# 1-Schematic_EEPROM_Writer.net
KiCad netlist of a schematic drawn in EasyEDA
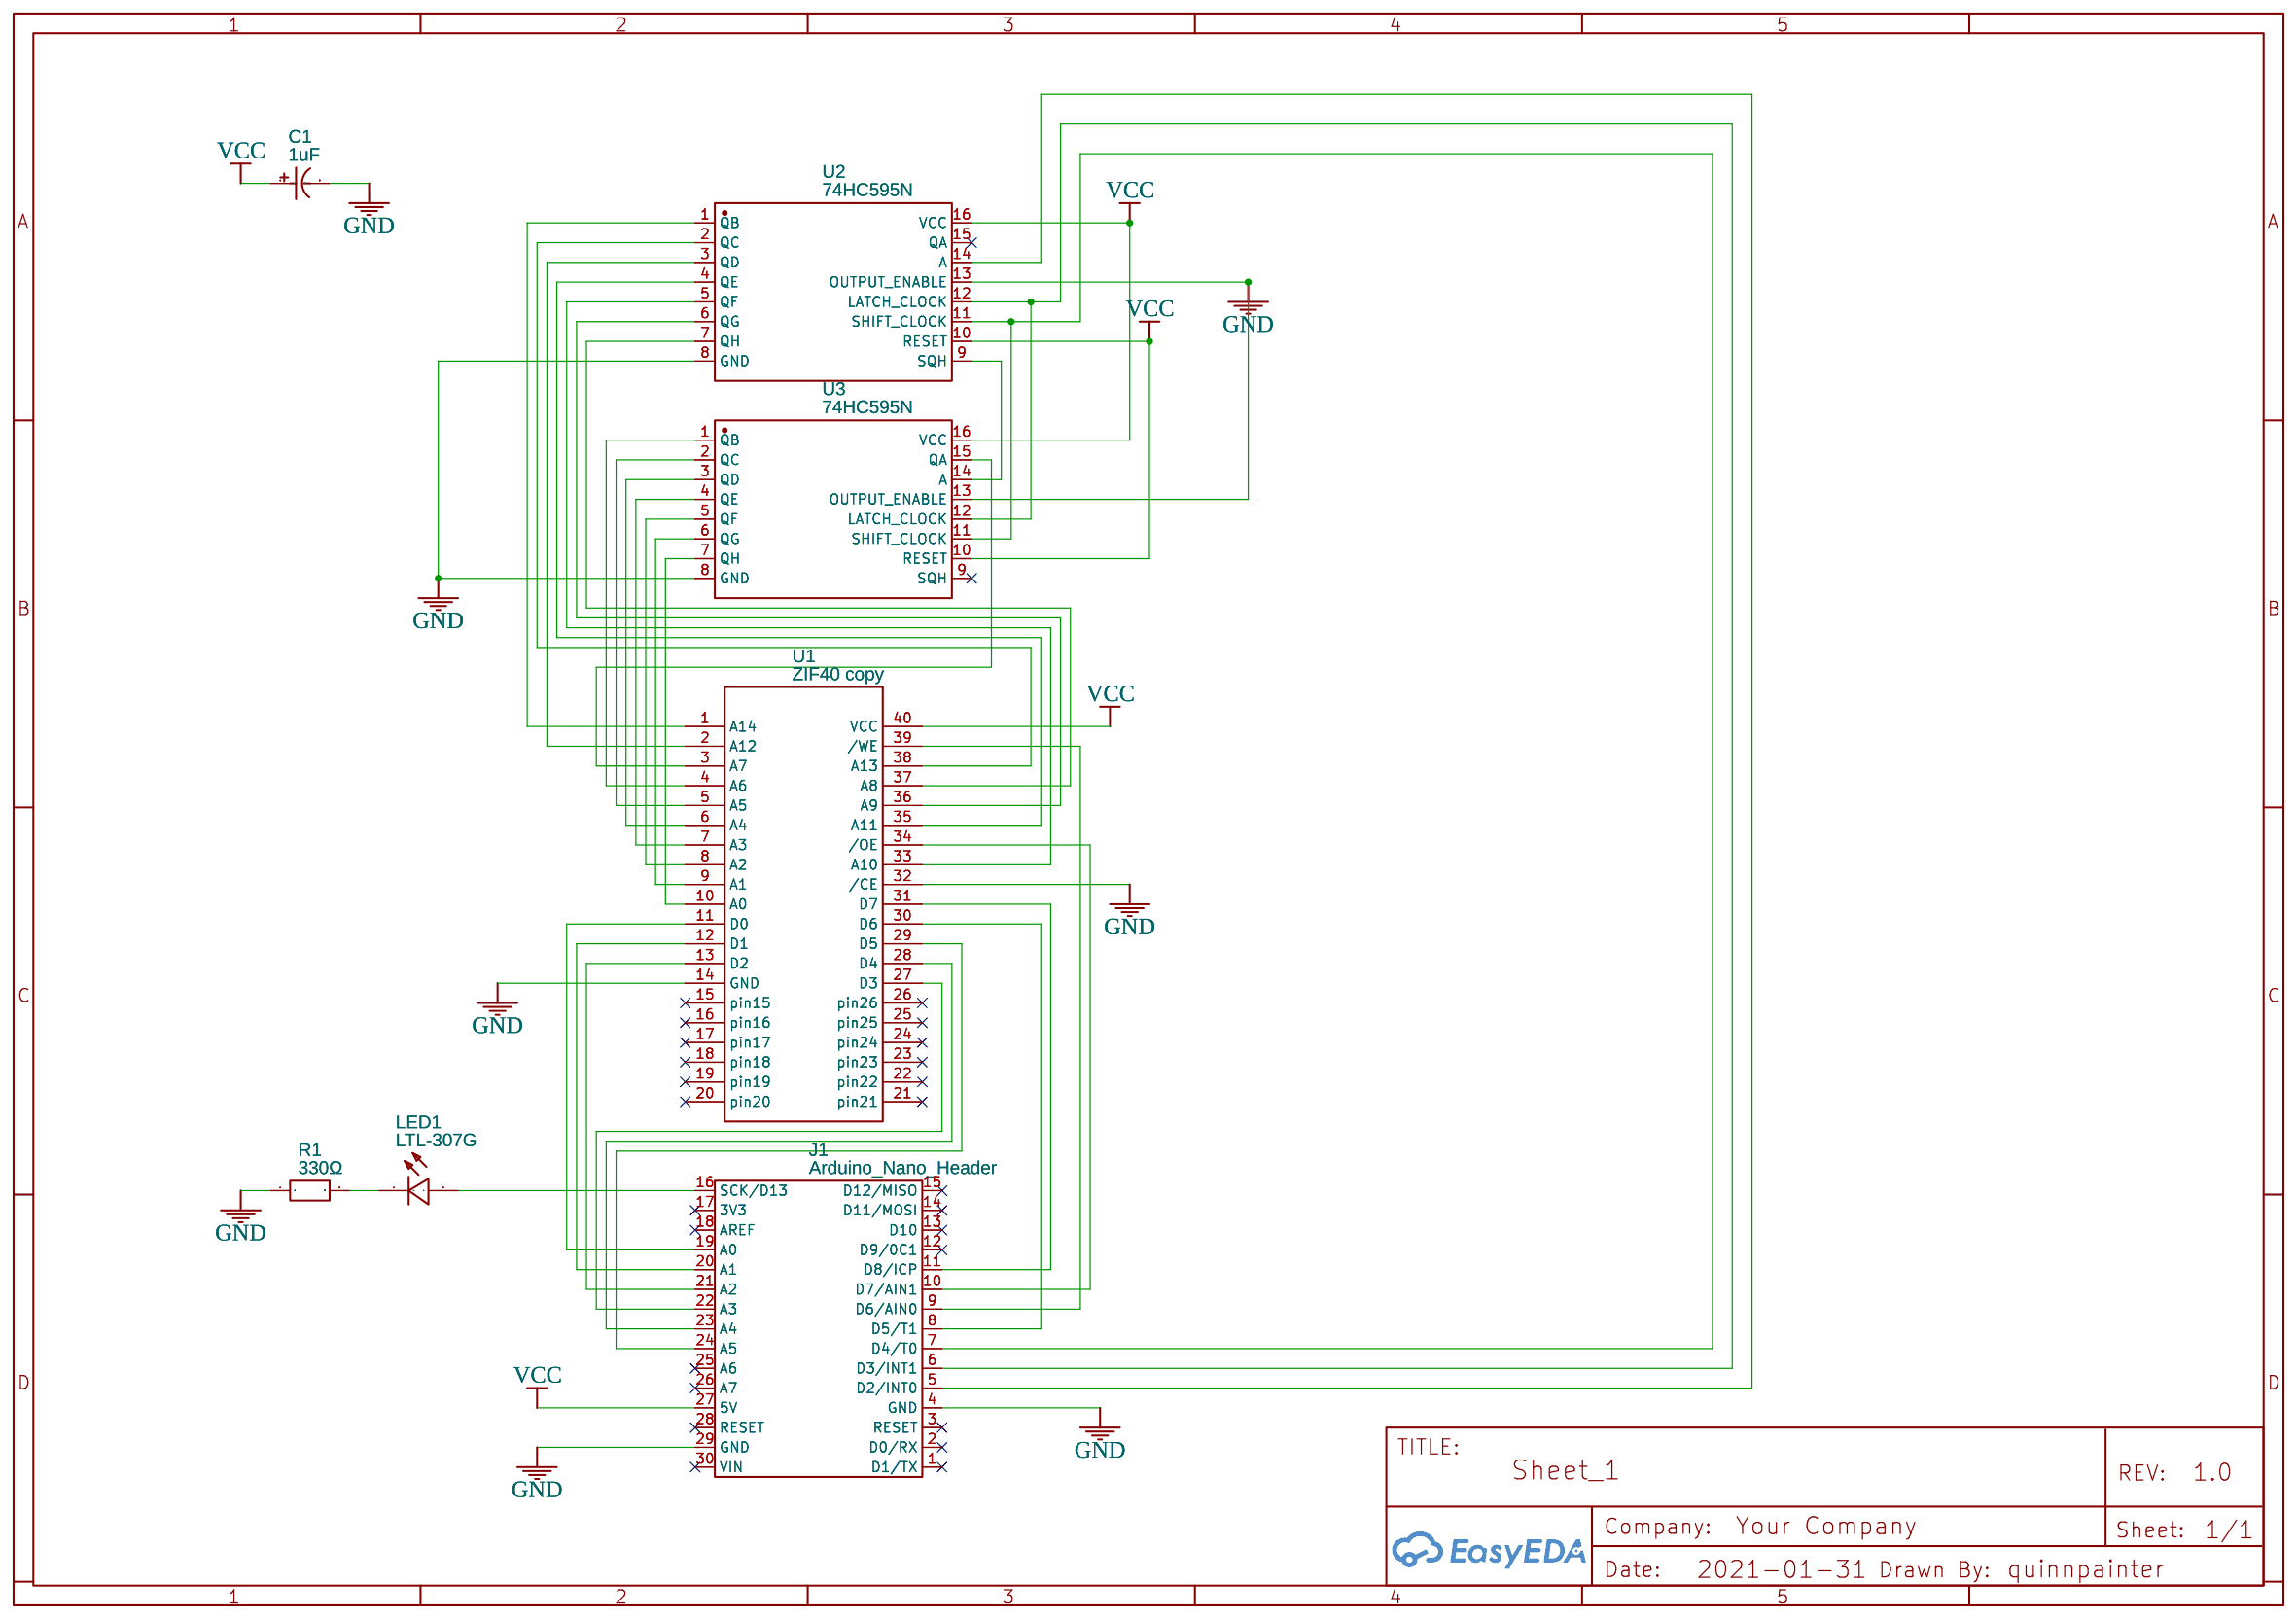
[diagram p0: schematic sheet]

(export (version "E")
  (design (tool "Eeschema 10.0.6"))
  (components
    (comp (ref "C1")
      (value "1uF")
      (fields
        (field (name "BOM_Manufacturer Part") "1uF 50V 4*5")
        (field (name "BOM_Supplier Part") "C47848")
      )
      (libsource (lib "") (part "1uF 50V 4*5"))
    )
    (comp (ref "J1") (value "Arduino_Nano_Header") (libsource (lib "") (part "Arduino_Nano_Header")))
    (comp (ref "LED1")
      (value "LTL-307G")
      (fields (field (name "BOM_Supplier Part") "C125080"))
      (libsource (lib "") (part "LTL-307G"))
    )
    (comp (ref "R1")
      (value "330Ω")
      (fields
        (field (name "BOM_Manufacturer Part") "MF1/4W-330Ω±1%T52")
        (field (name "BOM_Supplier Part") "C713986")
      )
      (libsource (lib "") (part "MF1/4W-330Ω±1%T52"))
    )
    (comp (ref "U1") (value "ZIF40 copy") (libsource (lib "") (part "ZIF40 copy")))
    (comp (ref "U2")
      (value "74HC595N")
      (fields (field (name "BOM_Supplier Part") "C507175"))
      (libsource (lib "") (part "74HC595N"))
    )
    (comp (ref "U3")
      (value "74HC595N")
      (fields (field (name "BOM_Supplier Part") "C507175"))
      (libsource (lib "") (part "74HC595N"))
    )
  )
  (nets
    (net (code "1") (name "GND") (class "Default")
      (node (ref "C1") (pin "2") (pinfunction "2_2") (pintype "input"))
      (node (ref "J1") (pin "29") (pinfunction "GND_29") (pintype "unspecified"))
      (node (ref "J1") (pin "4") (pinfunction "GND_4") (pintype "unspecified"))
      (node (ref "R1") (pin "1") (pinfunction "1_1") (pintype "unspecified"))
      (node (ref "U1") (pin "14") (pinfunction "GND_14") (pintype "output"))
      (node (ref "U1") (pin "32") (pinfunction "/CE_32") (pintype "bidirectional"))
      (node (ref "U2") (pin "13") (pinfunction "OUTPUT_ENABLE_13") (pintype "unspecified"))
      (node (ref "U2") (pin "8") (pinfunction "GND_8") (pintype "unspecified"))
      (node (ref "U3") (pin "13") (pinfunction "OUTPUT_ENABLE_13") (pintype "unspecified"))
      (node (ref "U3") (pin "8") (pinfunction "GND_8") (pintype "unspecified"))
    )
    (net (code "2") (name "Net-(J1-A0)") (class "Default")
      (node (ref "J1") (pin "19") (pinfunction "A0_19") (pintype "unspecified"))
      (node (ref "U1") (pin "11") (pinfunction "D0_11") (pintype "passive"))
    )
    (net (code "3") (name "Net-(J1-A1)") (class "Default")
      (node (ref "J1") (pin "20") (pinfunction "A1_20") (pintype "unspecified"))
      (node (ref "U1") (pin "12") (pinfunction "D1_12") (pintype "unspecified"))
    )
    (net (code "4") (name "Net-(J1-A2)") (class "Default")
      (node (ref "J1") (pin "21") (pinfunction "A2_21") (pintype "unspecified"))
      (node (ref "U1") (pin "13") (pinfunction "D2_13") (pintype "output"))
    )
    (net (code "5") (name "Net-(J1-A3)") (class "Default")
      (node (ref "J1") (pin "22") (pinfunction "A3_22") (pintype "unspecified"))
      (node (ref "U1") (pin "27") (pinfunction "D3_27") (pintype "unspecified"))
    )
    (net (code "6") (name "Net-(J1-A4)") (class "Default")
      (node (ref "J1") (pin "23") (pinfunction "A4_23") (pintype "unspecified"))
      (node (ref "U1") (pin "28") (pinfunction "D4_28") (pintype "passive"))
    )
    (net (code "7") (name "Net-(J1-A5)") (class "Default")
      (node (ref "J1") (pin "24") (pinfunction "A5_24") (pintype "unspecified"))
      (node (ref "U1") (pin "29") (pinfunction "D5_29") (pintype "bidirectional"))
    )
    (net (code "8") (name "Net-(J1-D2{slash}INT0)") (class "Default")
      (node (ref "J1") (pin "5") (pinfunction "D2/INT0_5") (pintype "unspecified"))
      (node (ref "U2") (pin "14") (pinfunction "A_14") (pintype "unspecified"))
    )
    (net (code "9") (name "Net-(J1-D3{slash}INT1)") (class "Default")
      (node (ref "J1") (pin "6") (pinfunction "D3/INT1_6") (pintype "unspecified"))
      (node (ref "U2") (pin "12") (pinfunction "LATCH_CLOCK_12") (pintype "unspecified"))
      (node (ref "U3") (pin "12") (pinfunction "LATCH_CLOCK_12") (pintype "unspecified"))
    )
    (net (code "10") (name "Net-(J1-D4{slash}T0)") (class "Default")
      (node (ref "J1") (pin "7") (pinfunction "D4/T0_7") (pintype "unspecified"))
      (node (ref "U2") (pin "11") (pinfunction "SHIFT_CLOCK_11") (pintype "unspecified"))
      (node (ref "U3") (pin "11") (pinfunction "SHIFT_CLOCK_11") (pintype "unspecified"))
    )
    (net (code "11") (name "Net-(J1-D5{slash}T1)") (class "Default")
      (node (ref "J1") (pin "8") (pinfunction "D5/T1_8") (pintype "unspecified"))
      (node (ref "U1") (pin "30") (pinfunction "D6_30") (pintype "bidirectional"))
    )
    (net (code "12") (name "Net-(J1-D6{slash}AIN0)") (class "Default")
      (node (ref "J1") (pin "9") (pinfunction "D6/AIN0_9") (pintype "unspecified"))
      (node (ref "U1") (pin "39") (pinfunction "/WE_39") (pintype "unspecified"))
    )
    (net (code "13") (name "Net-(J1-D7{slash}AIN1)") (class "Default")
      (node (ref "J1") (pin "10") (pinfunction "D7/AIN1_10") (pintype "unspecified"))
      (node (ref "U1") (pin "34") (pinfunction "/OE_34") (pintype "bidirectional"))
    )
    (net (code "14") (name "Net-(J1-D8{slash}ICP)") (class "Default")
      (node (ref "J1") (pin "11") (pinfunction "D8/ICP_11") (pintype "unspecified"))
      (node (ref "U1") (pin "31") (pinfunction "D7_31") (pintype "bidirectional"))
    )
    (net (code "15") (name "Net-(J1-SCK{slash}D13)") (class "Default")
      (node (ref "J1") (pin "16") (pinfunction "SCK/D13_16") (pintype "unspecified"))
      (node (ref "LED1") (pin "2") (pinfunction "+_2") (pintype "unspecified"))
    )
    (net (code "16") (name "Net-(LED1--)") (class "Default")
      (node (ref "LED1") (pin "1") (pinfunction "-_1") (pintype "unspecified"))
      (node (ref "R1") (pin "2") (pinfunction "2_2") (pintype "unspecified"))
    )
    (net (code "17") (name "Net-(U1-A0)") (class "Default")
      (node (ref "U1") (pin "10") (pinfunction "A0_10") (pintype "unspecified"))
      (node (ref "U3") (pin "7") (pinfunction "QH_7") (pintype "unspecified"))
    )
    (net (code "18") (name "Net-(U1-A1)") (class "Default")
      (node (ref "U1") (pin "9") (pinfunction "A1_9") (pintype "unspecified"))
      (node (ref "U3") (pin "6") (pinfunction "QG_6") (pintype "unspecified"))
    )
    (net (code "19") (name "Net-(U1-A2)") (class "Default")
      (node (ref "U1") (pin "8") (pinfunction "A2_8") (pintype "output"))
      (node (ref "U3") (pin "5") (pinfunction "QF_5") (pintype "unspecified"))
    )
    (net (code "20") (name "Net-(U1-A3)") (class "Default")
      (node (ref "U1") (pin "7") (pinfunction "A3_7") (pintype "unspecified"))
      (node (ref "U3") (pin "4") (pinfunction "QE_4") (pintype "unspecified"))
    )
    (net (code "21") (name "Net-(U1-A4)") (class "Default")
      (node (ref "U1") (pin "6") (pinfunction "A4_6") (pintype "unspecified"))
      (node (ref "U3") (pin "3") (pinfunction "QD_3") (pintype "unspecified"))
    )
    (net (code "22") (name "Net-(U1-A5)") (class "Default")
      (node (ref "U1") (pin "5") (pinfunction "A5_5") (pintype "unspecified"))
      (node (ref "U3") (pin "2") (pinfunction "QC_2") (pintype "unspecified"))
    )
    (net (code "23") (name "Net-(U1-A6)") (class "Default")
      (node (ref "U1") (pin "4") (pinfunction "A6_4") (pintype "unspecified"))
      (node (ref "U3") (pin "1") (pinfunction "QB_1") (pintype "unspecified"))
    )
    (net (code "24") (name "Net-(U1-A7)") (class "Default")
      (node (ref "U1") (pin "3") (pinfunction "A7_3") (pintype "unspecified"))
      (node (ref "U3") (pin "15") (pinfunction "QA_15") (pintype "unspecified"))
    )
    (net (code "25") (name "Net-(U1-A8)") (class "Default")
      (node (ref "U1") (pin "37") (pinfunction "A8_37") (pintype "unspecified"))
      (node (ref "U2") (pin "7") (pinfunction "QH_7") (pintype "unspecified"))
    )
    (net (code "26") (name "Net-(U1-A9)") (class "Default")
      (node (ref "U1") (pin "36") (pinfunction "A9_36") (pintype "bidirectional"))
      (node (ref "U2") (pin "6") (pinfunction "QG_6") (pintype "unspecified"))
    )
    (net (code "27") (name "Net-(U1-A10)") (class "Default")
      (node (ref "U1") (pin "33") (pinfunction "A10_33") (pintype "bidirectional"))
      (node (ref "U2") (pin "5") (pinfunction "QF_5") (pintype "unspecified"))
    )
    (net (code "28") (name "Net-(U1-A11)") (class "Default")
      (node (ref "U1") (pin "35") (pinfunction "A11_35") (pintype "bidirectional"))
      (node (ref "U2") (pin "4") (pinfunction "QE_4") (pintype "unspecified"))
    )
    (net (code "29") (name "Net-(U1-A12)") (class "Default")
      (node (ref "U1") (pin "2") (pinfunction "A12_2") (pintype "unspecified"))
      (node (ref "U2") (pin "3") (pinfunction "QD_3") (pintype "unspecified"))
    )
    (net (code "30") (name "Net-(U1-A13)") (class "Default")
      (node (ref "U1") (pin "38") (pinfunction "A13_38") (pintype "output"))
      (node (ref "U2") (pin "2") (pinfunction "QC_2") (pintype "unspecified"))
    )
    (net (code "31") (name "Net-(U1-A14)") (class "Default")
      (node (ref "U1") (pin "1") (pinfunction "A14_1") (pintype "unspecified"))
      (node (ref "U2") (pin "1") (pinfunction "QB_1") (pintype "unspecified"))
    )
    (net (code "32") (name "Net-(U2-SQH)") (class "Default")
      (node (ref "U2") (pin "9") (pinfunction "SQH_9") (pintype "unspecified"))
      (node (ref "U3") (pin "14") (pinfunction "A_14") (pintype "unspecified"))
    )
    (net (code "33") (name "VCC") (class "Default")
      (node (ref "C1") (pin "1") (pinfunction "1_1") (pintype "input"))
      (node (ref "J1") (pin "27") (pinfunction "5V_27") (pintype "unspecified"))
      (node (ref "U1") (pin "40") (pinfunction "VCC_40") (pintype "unspecified"))
      (node (ref "U2") (pin "10") (pinfunction "RESET_10") (pintype "unspecified"))
      (node (ref "U2") (pin "16") (pinfunction "VCC_16") (pintype "unspecified"))
      (node (ref "U3") (pin "10") (pinfunction "RESET_10") (pintype "unspecified"))
      (node (ref "U3") (pin "16") (pinfunction "VCC_16") (pintype "unspecified"))
    )
    (net (code "34") (name "unconnected-(J1-3V3-Pad17)") (class "Default")
      (node (ref "J1") (pin "17") (pinfunction "3V3_17") (pintype "unspecified+no_connect"))
    )
    (net (code "35") (name "unconnected-(J1-A6-Pad25)") (class "Default")
      (node (ref "J1") (pin "25") (pinfunction "A6_25") (pintype "unspecified+no_connect"))
    )
    (net (code "36") (name "unconnected-(J1-A7-Pad26)") (class "Default")
      (node (ref "J1") (pin "26") (pinfunction "A7_26") (pintype "unspecified+no_connect"))
    )
    (net (code "37") (name "unconnected-(J1-AREF-Pad18)") (class "Default")
      (node (ref "J1") (pin "18") (pinfunction "AREF_18") (pintype "unspecified+no_connect"))
    )
    (net (code "38") (name "unconnected-(J1-D0{slash}RX-Pad2)") (class "Default")
      (node (ref "J1") (pin "2") (pinfunction "D0/RX_2") (pintype "unspecified+no_connect"))
    )
    (net (code "39") (name "unconnected-(J1-D1{slash}TX-Pad1)") (class "Default")
      (node (ref "J1") (pin "1") (pinfunction "D1/TX_1") (pintype "unspecified+no_connect"))
    )
    (net (code "40") (name "unconnected-(J1-D9{slash}0C1-Pad12)") (class "Default")
      (node (ref "J1") (pin "12") (pinfunction "D9/0C1_12") (pintype "unspecified+no_connect"))
    )
    (net (code "41") (name "unconnected-(J1-D10-Pad13)") (class "Default")
      (node (ref "J1") (pin "13") (pinfunction "D10_13") (pintype "unspecified+no_connect"))
    )
    (net (code "42") (name "unconnected-(J1-D11{slash}MOSI-Pad14)") (class "Default")
      (node (ref "J1") (pin "14") (pinfunction "D11/MOSI_14") (pintype "unspecified+no_connect"))
    )
    (net (code "43") (name "unconnected-(J1-D12{slash}MISO-Pad15)") (class "Default")
      (node (ref "J1") (pin "15") (pinfunction "D12/MISO_15") (pintype "unspecified+no_connect"))
    )
    (net (code "44") (name "unconnected-(J1-RESET-Pad3)") (class "Default")
      (node (ref "J1") (pin "3") (pinfunction "RESET_3") (pintype "unspecified+no_connect"))
    )
    (net (code "45") (name "unconnected-(J1-RESET-Pad28)") (class "Default")
      (node (ref "J1") (pin "28") (pinfunction "RESET_28") (pintype "unspecified+no_connect"))
    )
    (net (code "46") (name "unconnected-(J1-VIN-Pad30)") (class "Default")
      (node (ref "J1") (pin "30") (pinfunction "VIN_30") (pintype "unspecified+no_connect"))
    )
    (net (code "47") (name "unconnected-(U1-pin15-Pad15)") (class "Default")
      (node (ref "U1") (pin "15") (pinfunction "pin15_15") (pintype "output+no_connect"))
    )
    (net (code "48") (name "unconnected-(U1-pin16-Pad16)") (class "Default")
      (node (ref "U1") (pin "16") (pinfunction "pin16_16") (pintype "output+no_connect"))
    )
    (net (code "49") (name "unconnected-(U1-pin17-Pad17)") (class "Default")
      (node (ref "U1") (pin "17") (pinfunction "pin17_17") (pintype "unspecified+no_connect"))
    )
    (net (code "50") (name "unconnected-(U1-pin18-Pad18)") (class "Default")
      (node (ref "U1") (pin "18") (pinfunction "pin18_18") (pintype "unspecified+no_connect"))
    )
    (net (code "51") (name "unconnected-(U1-pin19-Pad19)") (class "Default")
      (node (ref "U1") (pin "19") (pinfunction "pin19_19") (pintype "unspecified+no_connect"))
    )
    (net (code "52") (name "unconnected-(U1-pin20-Pad20)") (class "Default")
      (node (ref "U1") (pin "20") (pinfunction "pin20_20") (pintype "unspecified+no_connect"))
    )
    (net (code "53") (name "unconnected-(U1-pin21-Pad21)") (class "Default")
      (node (ref "U1") (pin "21") (pinfunction "pin21_21") (pintype "bidirectional+no_connect"))
    )
    (net (code "54") (name "unconnected-(U1-pin22-Pad22)") (class "Default")
      (node (ref "U1") (pin "22") (pinfunction "pin22_22") (pintype "output+no_connect"))
    )
    (net (code "55") (name "unconnected-(U1-pin23-Pad23)") (class "Default")
      (node (ref "U1") (pin "23") (pinfunction "pin23_23") (pintype "output+no_connect"))
    )
    (net (code "56") (name "unconnected-(U1-pin24-Pad24)") (class "Default")
      (node (ref "U1") (pin "24") (pinfunction "pin24_24") (pintype "output+no_connect"))
    )
    (net (code "57") (name "unconnected-(U1-pin25-Pad25)") (class "Default")
      (node (ref "U1") (pin "25") (pinfunction "pin25_25") (pintype "output+no_connect"))
    )
    (net (code "58") (name "unconnected-(U1-pin26-Pad26)") (class "Default")
      (node (ref "U1") (pin "26") (pinfunction "pin26_26") (pintype "unspecified+no_connect"))
    )
    (net (code "59") (name "unconnected-(U2-QA-Pad15)") (class "Default")
      (node (ref "U2") (pin "15") (pinfunction "QA_15") (pintype "unspecified+no_connect"))
    )
    (net (code "60") (name "unconnected-(U3-SQH-Pad9)") (class "Default")
      (node (ref "U3") (pin "9") (pinfunction "SQH_9") (pintype "unspecified+no_connect"))
    )
  )
)
